# Connector.net
KiCad netlist of a schematic drawn in Altium Designer
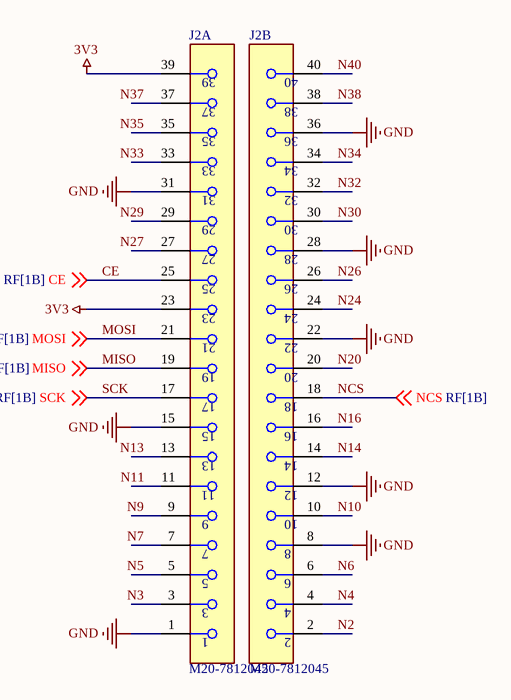
[diagram p0: Connector.SchDoc]

(export (version "E")
  (design (tool "Eeschema 10.0.6"))
  (components
    (comp (ref "J2")
      (value "M20-7812045")
      (footprint "FP-M20-7812045-MFG")
      (description "CONN RCPT 40POS 0.1 GOLD SMD")
      (libsource (lib "Altium Content Vault") (part "7acf1c4a8db21028d11741a46a6ec78"))
    )
  )
  (nets
    (net (code "1") (name "/N2") (class "Default")
      (node (ref "J2") (pin "2") (pinfunction "2_2") (pintype "passive"))
    )
    (net (code "2") (name "/N3") (class "Default")
      (node (ref "J2") (pin "3") (pinfunction "3_3") (pintype "passive"))
    )
    (net (code "3") (name "/N4") (class "Default")
      (node (ref "J2") (pin "4") (pinfunction "4_4") (pintype "passive"))
    )
    (net (code "4") (name "/N5") (class "Default")
      (node (ref "J2") (pin "5") (pinfunction "5_5") (pintype "passive"))
    )
    (net (code "5") (name "/N6") (class "Default")
      (node (ref "J2") (pin "6") (pinfunction "6_6") (pintype "passive"))
    )
    (net (code "6") (name "/N7") (class "Default")
      (node (ref "J2") (pin "7") (pinfunction "7_7") (pintype "passive"))
    )
    (net (code "7") (name "/N9") (class "Default")
      (node (ref "J2") (pin "9") (pinfunction "9_9") (pintype "passive"))
    )
    (net (code "8") (name "/N10") (class "Default")
      (node (ref "J2") (pin "10") (pinfunction "10_10") (pintype "passive"))
    )
    (net (code "9") (name "/N11") (class "Default")
      (node (ref "J2") (pin "11") (pinfunction "11_11") (pintype "passive"))
    )
    (net (code "10") (name "/N13") (class "Default")
      (node (ref "J2") (pin "13") (pinfunction "13_13") (pintype "passive"))
    )
    (net (code "11") (name "/N14") (class "Default")
      (node (ref "J2") (pin "14") (pinfunction "14_14") (pintype "passive"))
    )
    (net (code "12") (name "/N16") (class "Default")
      (node (ref "J2") (pin "16") (pinfunction "16_16") (pintype "passive"))
    )
    (net (code "13") (name "/N20") (class "Default")
      (node (ref "J2") (pin "20") (pinfunction "20_20") (pintype "passive"))
    )
    (net (code "14") (name "/N24") (class "Default")
      (node (ref "J2") (pin "24") (pinfunction "24_24") (pintype "passive"))
    )
    (net (code "15") (name "/N26") (class "Default")
      (node (ref "J2") (pin "26") (pinfunction "26_26") (pintype "passive"))
    )
    (net (code "16") (name "/N27") (class "Default")
      (node (ref "J2") (pin "27") (pinfunction "27_27") (pintype "passive"))
    )
    (net (code "17") (name "/N29") (class "Default")
      (node (ref "J2") (pin "29") (pinfunction "29_29") (pintype "passive"))
    )
    (net (code "18") (name "/N30") (class "Default")
      (node (ref "J2") (pin "30") (pinfunction "30_30") (pintype "passive"))
    )
    (net (code "19") (name "/N32") (class "Default")
      (node (ref "J2") (pin "32") (pinfunction "32_32") (pintype "passive"))
    )
    (net (code "20") (name "/N33") (class "Default")
      (node (ref "J2") (pin "33") (pinfunction "33_33") (pintype "passive"))
    )
    (net (code "21") (name "/N34") (class "Default")
      (node (ref "J2") (pin "34") (pinfunction "34_34") (pintype "passive"))
    )
    (net (code "22") (name "/N35") (class "Default")
      (node (ref "J2") (pin "35") (pinfunction "35_35") (pintype "passive"))
    )
    (net (code "23") (name "/N37") (class "Default")
      (node (ref "J2") (pin "37") (pinfunction "37_37") (pintype "passive"))
    )
    (net (code "24") (name "/N38") (class "Default")
      (node (ref "J2") (pin "38") (pinfunction "38_38") (pintype "passive"))
    )
    (net (code "25") (name "/N40") (class "Default")
      (node (ref "J2") (pin "40") (pinfunction "40_40") (pintype "passive"))
    )
    (net (code "26") (name "3V3") (class "Default")
      (node (ref "J2") (pin "23") (pinfunction "23_23") (pintype "passive"))
      (node (ref "J2") (pin "39") (pinfunction "39_39") (pintype "passive"))
    )
    (net (code "27") (name "CE") (class "Default")
      (node (ref "J2") (pin "25") (pinfunction "25_25") (pintype "passive"))
    )
    (net (code "28") (name "GND") (class "Default")
      (node (ref "J2") (pin "1") (pinfunction "1_1") (pintype "passive"))
      (node (ref "J2") (pin "12") (pinfunction "12_12") (pintype "passive"))
      (node (ref "J2") (pin "15") (pinfunction "15_15") (pintype "passive"))
      (node (ref "J2") (pin "22") (pinfunction "22_22") (pintype "passive"))
      (node (ref "J2") (pin "28") (pinfunction "28_28") (pintype "passive"))
      (node (ref "J2") (pin "31") (pinfunction "31_31") (pintype "passive"))
      (node (ref "J2") (pin "36") (pinfunction "36_36") (pintype "passive"))
      (node (ref "J2") (pin "8") (pinfunction "8_8") (pintype "passive"))
    )
    (net (code "29") (name "MISO") (class "Default")
      (node (ref "J2") (pin "19") (pinfunction "19_19") (pintype "passive"))
    )
    (net (code "30") (name "MOSI") (class "Default")
      (node (ref "J2") (pin "21") (pinfunction "21_21") (pintype "passive"))
    )
    (net (code "31") (name "NCS") (class "Default")
      (node (ref "J2") (pin "18") (pinfunction "18_18") (pintype "passive"))
    )
    (net (code "32") (name "SCK") (class "Default")
      (node (ref "J2") (pin "17") (pinfunction "17_17") (pintype "passive"))
    )
  )
)
